# connectors.net
KiCad netlist of a schematic drawn in Altium Designer
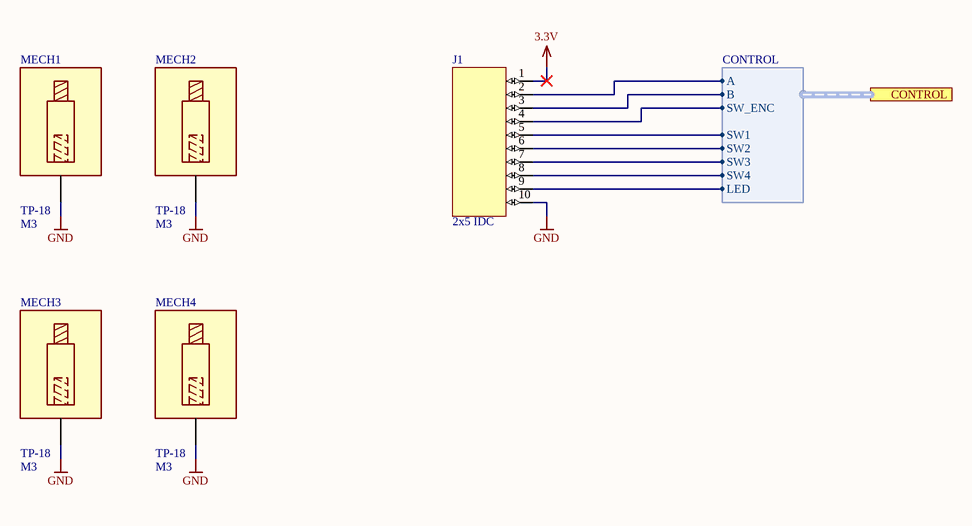
[diagram p0: connectors.SchDoc]

(export (version "E")
  (design (tool "Eeschema 10.0.6"))
  (components
    (comp (ref "J1")
      (value "2x5 IDC")
      (footprint "IDC_2x5")
      (description "2x5 IDC Header")
      (libsource (lib "soldering_station") (part "IDC_2x5"))
    )
    (comp (ref "MECH1")
      (value "TP-18")
      (footprint "MECH_SPACER_MALE_FEMALE_18MM_M3")
      (fields
        (field (name "PART NUMBER") "MECH_SPACER_MALE_FEMALE_18MM_M3")
        (field (name "SCH_FOOTPRINT") "M3")
        (field (name "MANUFACTURER") "FIX&FASTEN")
        (field (name "Comment") "M3X0.5")
      )
      (libsource (lib "Library") (part "MECH_SPACER_MALE_FEMALE"))
    )
    (comp (ref "MECH2")
      (value "TP-18")
      (footprint "MECH_SPACER_MALE_FEMALE_18MM_M3")
      (fields
        (field (name "PART NUMBER") "MECH_SPACER_MALE_FEMALE_18MM_M3")
        (field (name "SCH_FOOTPRINT") "M3")
        (field (name "MANUFACTURER") "FIX&FASTEN")
        (field (name "Comment") "M3X0.5")
      )
      (libsource (lib "Library") (part "MECH_SPACER_MALE_FEMALE"))
    )
    (comp (ref "MECH3")
      (value "TP-18")
      (footprint "MECH_SPACER_MALE_FEMALE_18MM_M3")
      (fields
        (field (name "PART NUMBER") "MECH_SPACER_MALE_FEMALE_18MM_M3")
        (field (name "SCH_FOOTPRINT") "M3")
        (field (name "MANUFACTURER") "FIX&FASTEN")
        (field (name "Comment") "M3X0.5")
      )
      (libsource (lib "Library") (part "MECH_SPACER_MALE_FEMALE"))
    )
    (comp (ref "MECH4")
      (value "TP-18")
      (footprint "MECH_SPACER_MALE_FEMALE_18MM_M3")
      (fields
        (field (name "PART NUMBER") "MECH_SPACER_MALE_FEMALE_18MM_M3")
        (field (name "SCH_FOOTPRINT") "M3")
        (field (name "MANUFACTURER") "FIX&FASTEN")
        (field (name "Comment") "M3X0.5")
      )
      (libsource (lib "Library") (part "MECH_SPACER_MALE_FEMALE"))
    )
  )
  (nets
    (net (code "2") (name "/A") (class "Default") (node (ref "J1") (pin "2") (pintype "bidirectional")))
    (net (code "3") (name "/B") (class "Default") (node (ref "J1") (pin "3") (pintype "bidirectional")))
    (net (code "4") (name "/LED") (class "Default") (node (ref "J1") (pin "9") (pintype "bidirectional")))
    (net (code "5") (name "/SW1") (class "Default") (node (ref "J1") (pin "5") (pintype "bidirectional")))
    (net (code "6") (name "/SW2") (class "Default") (node (ref "J1") (pin "6") (pintype "bidirectional")))
    (net (code "7") (name "/SW3") (class "Default") (node (ref "J1") (pin "7") (pintype "bidirectional")))
    (net (code "8") (name "/SW4") (class "Default") (node (ref "J1") (pin "8") (pintype "bidirectional")))
    (net (code "9") (name "/SW_ENC") (class "Default") (node (ref "J1") (pin "4") (pintype "bidirectional")))
    (net (code "11") (name "3.3V") (class "Default") (node (ref "J1") (pin "1") (pintype "bidirectional")))
    (net (code "12") (name "GND") (class "Default")
      (node (ref "J1") (pin "10") (pintype "bidirectional"))
      (node (ref "MECH1") (pin "1") (pintype "passive"))
      (node (ref "MECH2") (pin "1") (pintype "passive"))
      (node (ref "MECH3") (pin "1") (pintype "passive"))
      (node (ref "MECH4") (pin "1") (pintype "passive"))
    )
  )
)
